# 3UP_v1.net
KiCad netlist of a schematic drawn in EAGLE
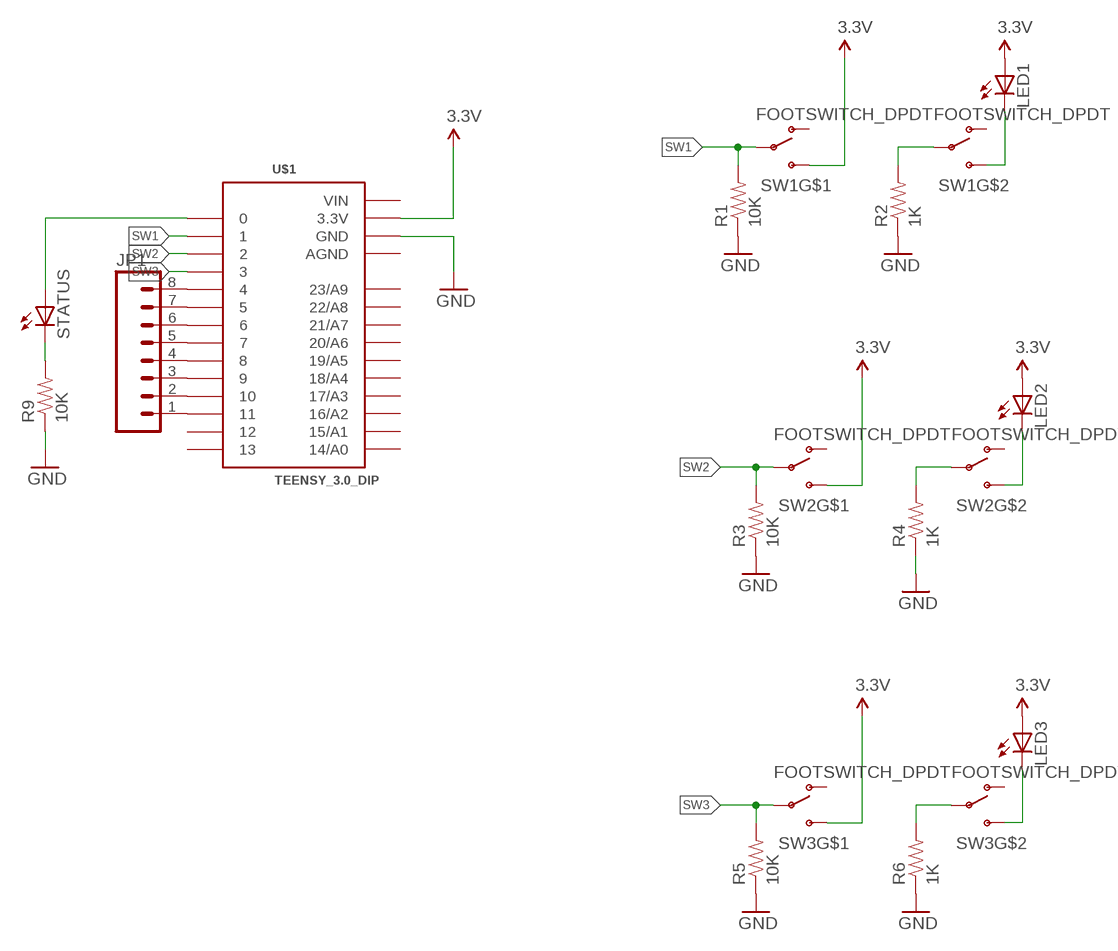
[diagram p0: schematic, sheet 1]

(export (version "E")
  (design (tool "Eeschema 10.0.6"))
  (components
    (comp (ref "JP1")
      (value "M08NO_SILK")
      (footprint "eagle-import:1X08_NO_SILK")
      (libsource (lib "eagle-import") (part "M08NO_SILK"))
    )
    (comp (ref "LED1")
      (value "LED5MM-W/STENCIL")
      (footprint "eagle-import:LED5MM-STENCILHOLE")
      (libsource (lib "eagle-import") (part "LED5MM-W/STENCIL"))
    )
    (comp (ref "LED2")
      (value "LED5MM-W/STENCIL")
      (footprint "eagle-import:LED5MM-STENCILHOLE")
      (libsource (lib "eagle-import") (part "LED5MM-W/STENCIL"))
    )
    (comp (ref "LED3")
      (value "LED5MM-W/STENCIL")
      (footprint "eagle-import:LED5MM-STENCILHOLE")
      (libsource (lib "eagle-import") (part "LED5MM-W/STENCIL"))
    )
    (comp (ref "R1")
      (value "10K")
      (footprint "eagle-import:0805")
      (libsource (lib "eagle-import") (part "RESISTOR0805-RES"))
    )
    (comp (ref "R2")
      (value "1K")
      (footprint "eagle-import:0805")
      (libsource (lib "eagle-import") (part "RESISTOR0805-RES"))
    )
    (comp (ref "R3")
      (value "10K")
      (footprint "eagle-import:0805")
      (libsource (lib "eagle-import") (part "RESISTOR0805-RES"))
    )
    (comp (ref "R4")
      (value "1K")
      (footprint "eagle-import:0805")
      (libsource (lib "eagle-import") (part "RESISTOR0805-RES"))
    )
    (comp (ref "R5")
      (value "10K")
      (footprint "eagle-import:0805")
      (libsource (lib "eagle-import") (part "RESISTOR0805-RES"))
    )
    (comp (ref "R6")
      (value "1K")
      (footprint "eagle-import:0805")
      (libsource (lib "eagle-import") (part "RESISTOR0805-RES"))
    )
    (comp (ref "R9")
      (value "10K")
      (footprint "eagle-import:0805")
      (libsource (lib "eagle-import") (part "RESISTOR0805-RES"))
    )
    (comp (ref "STATUS")
      (value "LED5MM-W/STENCIL")
      (footprint "eagle-import:LED5MM-STENCILHOLE")
      (libsource (lib "eagle-import") (part "LED5MM-W/STENCIL"))
    )
    (comp (ref "SW1")
      (value "FOOTSWITCH_DPDT")
      (footprint "eagle-import:FOOTSWITCH")
      (libsource (lib "eagle-import") (part "FOOTSWITCH_DPDT"))
    )
    (comp (ref "SW2")
      (value "FOOTSWITCH_DPDT")
      (footprint "eagle-import:FOOTSWITCH")
      (libsource (lib "eagle-import") (part "FOOTSWITCH_DPDT"))
    )
    (comp (ref "SW3")
      (value "FOOTSWITCH_DPDT")
      (footprint "eagle-import:FOOTSWITCH")
      (libsource (lib "eagle-import") (part "FOOTSWITCH_DPDT"))
    )
    (comp (ref "U$1")
      (value "TEENSY_3.0_DIP")
      (footprint "eagle-import:TEENSY_3.0_DIP")
      (libsource (lib "eagle-import") (part "TEENSY_3.0_DIP"))
    )
  )
  (nets
    (net (code "1") (name "/AGND") (class "Default")
      (node (ref "U$1") (pin "AGND") (pinfunction "AGND_AGND") (pintype "power_in"))
    )
    (net (code "2") (name "/VIN") (class "Default")
      (node (ref "U$1") (pin "VIN") (pinfunction "VIN_VIN") (pintype "power_in"))
    )
    (net (code "3") (name "3.3V") (class "Default")
      (node (ref "LED1") (pin "A") (pinfunction "A_A") (pintype "passive"))
      (node (ref "LED2") (pin "A") (pinfunction "A_A") (pintype "passive"))
      (node (ref "LED3") (pin "A") (pinfunction "A_A") (pintype "passive"))
      (node (ref "SW1") (pin "P$3") (pinfunction "S_P$3") (pintype "passive"))
      (node (ref "SW2") (pin "P$3") (pinfunction "S_P$3") (pintype "passive"))
      (node (ref "SW3") (pin "P$3") (pinfunction "S_P$3") (pintype "passive"))
      (node (ref "U$1") (pin "3.3V") (pinfunction "3.3V_3.3V") (pintype "power_in"))
    )
    (net (code "4") (name "GND") (class "Default")
      (node (ref "R1") (pin "1") (pinfunction "1_1") (pintype "passive"))
      (node (ref "R2") (pin "1") (pinfunction "1_1") (pintype "passive"))
      (node (ref "R3") (pin "1") (pinfunction "1_1") (pintype "passive"))
      (node (ref "R4") (pin "1") (pinfunction "1_1") (pintype "passive"))
      (node (ref "R5") (pin "1") (pinfunction "1_1") (pintype "passive"))
      (node (ref "R6") (pin "1") (pinfunction "1_1") (pintype "passive"))
      (node (ref "R9") (pin "1") (pinfunction "1_1") (pintype "passive"))
      (node (ref "U$1") (pin "GND") (pinfunction "GND_GND") (pintype "power_in"))
    )
    (net (code "5") (name "Net-(JP1-Pad1)") (class "Default")
      (node (ref "JP1") (pin "1") (pinfunction "1_1") (pintype "passive"))
      (node (ref "U$1") (pin "11") (pinfunction "11_11") (pintype "bidirectional"))
    )
    (net (code "6") (name "Net-(JP1-Pad2)") (class "Default")
      (node (ref "JP1") (pin "2") (pinfunction "2_2") (pintype "passive"))
      (node (ref "U$1") (pin "10") (pinfunction "10_10") (pintype "bidirectional"))
    )
    (net (code "7") (name "Net-(JP1-Pad3)") (class "Default")
      (node (ref "JP1") (pin "3") (pinfunction "3_3") (pintype "passive"))
      (node (ref "U$1") (pin "9") (pinfunction "9_9") (pintype "bidirectional"))
    )
    (net (code "8") (name "Net-(JP1-Pad4)") (class "Default")
      (node (ref "JP1") (pin "4") (pinfunction "4_4") (pintype "passive"))
      (node (ref "U$1") (pin "8") (pinfunction "8_8") (pintype "bidirectional"))
    )
    (net (code "9") (name "Net-(JP1-Pad5)") (class "Default")
      (node (ref "JP1") (pin "5") (pinfunction "5_5") (pintype "passive"))
      (node (ref "U$1") (pin "7") (pinfunction "7_7") (pintype "bidirectional"))
    )
    (net (code "10") (name "Net-(JP1-Pad6)") (class "Default")
      (node (ref "JP1") (pin "6") (pinfunction "6_6") (pintype "passive"))
      (node (ref "U$1") (pin "6") (pinfunction "6_6") (pintype "bidirectional"))
    )
    (net (code "11") (name "Net-(JP1-Pad7)") (class "Default")
      (node (ref "JP1") (pin "7") (pinfunction "7_7") (pintype "passive"))
      (node (ref "U$1") (pin "5") (pinfunction "5_5") (pintype "bidirectional"))
    )
    (net (code "12") (name "Net-(JP1-Pad8)") (class "Default")
      (node (ref "JP1") (pin "8") (pinfunction "8_8") (pintype "passive"))
      (node (ref "U$1") (pin "4") (pinfunction "4_4") (pintype "bidirectional"))
    )
    (net (code "13") (name "Net-(LED1-C)") (class "Default")
      (node (ref "LED1") (pin "K") (pinfunction "C_K") (pintype "passive"))
      (node (ref "SW1") (pin "P$6") (pinfunction "S_P$6") (pintype "passive"))
    )
    (net (code "14") (name "Net-(LED2-C)") (class "Default")
      (node (ref "LED2") (pin "K") (pinfunction "C_K") (pintype "passive"))
      (node (ref "SW2") (pin "P$6") (pinfunction "S_P$6") (pintype "passive"))
    )
    (net (code "15") (name "Net-(LED3-C)") (class "Default")
      (node (ref "LED3") (pin "K") (pinfunction "C_K") (pintype "passive"))
      (node (ref "SW3") (pin "P$6") (pinfunction "S_P$6") (pintype "passive"))
    )
    (net (code "16") (name "Net-(STATUS-C)") (class "Default")
      (node (ref "R9") (pin "2") (pinfunction "2_2") (pintype "passive"))
      (node (ref "STATUS") (pin "K") (pinfunction "C_K") (pintype "passive"))
    )
    (net (code "17") (name "Net-(STATUS-PadA)") (class "Default")
      (node (ref "STATUS") (pin "A") (pinfunction "A_A") (pintype "passive"))
      (node (ref "U$1") (pin "0") (pinfunction "0_0") (pintype "bidirectional"))
    )
    (net (code "18") (name "Net-(SW1B-P)") (class "Default")
      (node (ref "R2") (pin "2") (pinfunction "2_2") (pintype "passive"))
      (node (ref "SW1") (pin "P$5") (pinfunction "P_P$5") (pintype "passive"))
    )
    (net (code "19") (name "Net-(SW2B-P)") (class "Default")
      (node (ref "R4") (pin "2") (pinfunction "2_2") (pintype "passive"))
      (node (ref "SW2") (pin "P$5") (pinfunction "P_P$5") (pintype "passive"))
    )
    (net (code "20") (name "Net-(SW3B-P)") (class "Default")
      (node (ref "R6") (pin "2") (pinfunction "2_2") (pintype "passive"))
      (node (ref "SW3") (pin "P$5") (pinfunction "P_P$5") (pintype "passive"))
    )
    (net (code "21") (name "SW1") (class "Default")
      (node (ref "R1") (pin "2") (pinfunction "2_2") (pintype "passive"))
      (node (ref "SW1") (pin "P$2") (pinfunction "P_P$2") (pintype "passive"))
      (node (ref "U$1") (pin "1") (pinfunction "1_1") (pintype "bidirectional"))
    )
    (net (code "22") (name "SW2") (class "Default")
      (node (ref "R3") (pin "2") (pinfunction "2_2") (pintype "passive"))
      (node (ref "SW2") (pin "P$2") (pinfunction "P_P$2") (pintype "passive"))
      (node (ref "U$1") (pin "2") (pinfunction "2_2") (pintype "bidirectional"))
    )
    (net (code "23") (name "SW3") (class "Default")
      (node (ref "R5") (pin "2") (pinfunction "2_2") (pintype "passive"))
      (node (ref "SW3") (pin "P$2") (pinfunction "P_P$2") (pintype "passive"))
      (node (ref "U$1") (pin "3") (pinfunction "3_3") (pintype "bidirectional"))
    )
    (net (code "24") (name "unconnected-(SW1A-O-PadP$1)") (class "Default")
      (node (ref "SW1") (pin "P$1") (pinfunction "O_P$1") (pintype "passive"))
    )
    (net (code "25") (name "unconnected-(SW1B-O-PadP$4)") (class "Default")
      (node (ref "SW1") (pin "P$4") (pinfunction "O_P$4") (pintype "passive"))
    )
    (net (code "26") (name "unconnected-(SW2A-O-PadP$1)") (class "Default")
      (node (ref "SW2") (pin "P$1") (pinfunction "O_P$1") (pintype "passive"))
    )
    (net (code "27") (name "unconnected-(SW2B-O-PadP$4)") (class "Default")
      (node (ref "SW2") (pin "P$4") (pinfunction "O_P$4") (pintype "passive"))
    )
    (net (code "28") (name "unconnected-(SW3A-O-PadP$1)") (class "Default")
      (node (ref "SW3") (pin "P$1") (pinfunction "O_P$1") (pintype "passive"))
    )
    (net (code "29") (name "unconnected-(SW3B-O-PadP$4)") (class "Default")
      (node (ref "SW3") (pin "P$4") (pinfunction "O_P$4") (pintype "passive"))
    )
    (net (code "30") (name "unconnected-(U$1-Pad12)") (class "Default")
      (node (ref "U$1") (pin "12") (pinfunction "12_12") (pintype "bidirectional"))
    )
    (net (code "31") (name "unconnected-(U$1-Pad13)") (class "Default")
      (node (ref "U$1") (pin "13") (pinfunction "13_13") (pintype "bidirectional"))
    )
    (net (code "32") (name "unconnected-(U$1-Pad14{slash}A0)") (class "Default")
      (node (ref "U$1") (pin "14/A0") (pinfunction "14/A0_14/A0") (pintype "bidirectional"))
    )
    (net (code "33") (name "unconnected-(U$1-Pad15{slash}A1)") (class "Default")
      (node (ref "U$1") (pin "15/A1") (pinfunction "15/A1_15/A1") (pintype "bidirectional"))
    )
    (net (code "34") (name "unconnected-(U$1-Pad16{slash}A2)") (class "Default")
      (node (ref "U$1") (pin "16/A2") (pinfunction "16/A2_16/A2") (pintype "bidirectional"))
    )
    (net (code "35") (name "unconnected-(U$1-Pad17{slash}A3)") (class "Default")
      (node (ref "U$1") (pin "17/A3") (pinfunction "17/A3_17/A3") (pintype "bidirectional"))
    )
    (net (code "36") (name "unconnected-(U$1-Pad18{slash}A4)") (class "Default")
      (node (ref "U$1") (pin "18/A4") (pinfunction "18/A4_18/A4") (pintype "bidirectional"))
    )
    (net (code "37") (name "unconnected-(U$1-Pad19{slash}A5)") (class "Default")
      (node (ref "U$1") (pin "19/A5") (pinfunction "19/A5_19/A5") (pintype "bidirectional"))
    )
    (net (code "38") (name "unconnected-(U$1-Pad20{slash}A6)") (class "Default")
      (node (ref "U$1") (pin "20/A6") (pinfunction "20/A6_20/A6") (pintype "bidirectional"))
    )
    (net (code "39") (name "unconnected-(U$1-Pad21{slash}A7)") (class "Default")
      (node (ref "U$1") (pin "21/A7") (pinfunction "21/A7_21/A7") (pintype "bidirectional"))
    )
    (net (code "40") (name "unconnected-(U$1-Pad22{slash}A8)") (class "Default")
      (node (ref "U$1") (pin "22/A8") (pinfunction "22/A8_22/A8") (pintype "bidirectional"))
    )
    (net (code "41") (name "unconnected-(U$1-Pad23{slash}A9)") (class "Default")
      (node (ref "U$1") (pin "23/A9") (pinfunction "23/A9_23/A9") (pintype "bidirectional"))
    )
  )
)
